# TestMule_2015.net
KiCad netlist of a schematic drawn in EAGLE
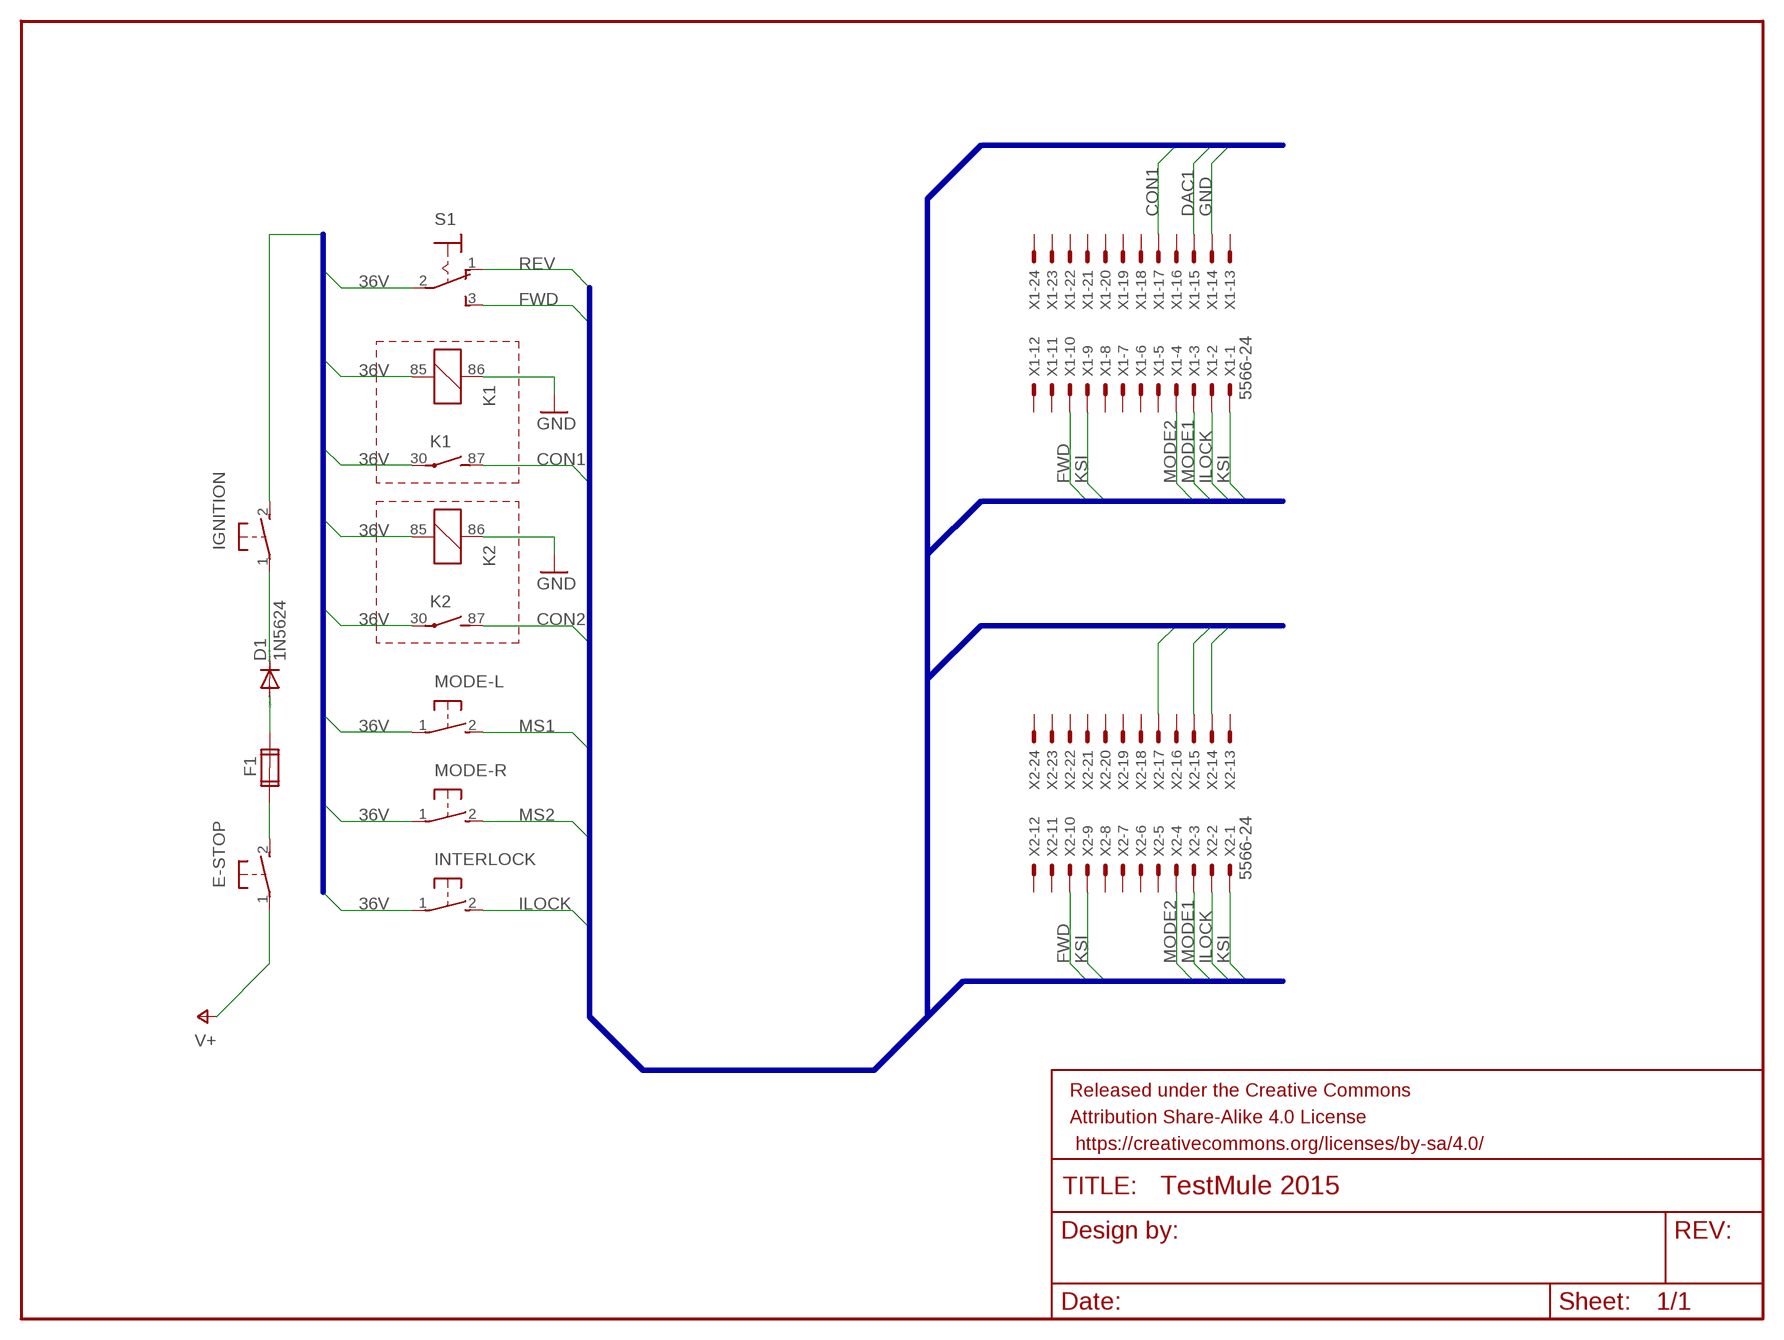
[diagram p0: schematic, sheet 1]

(export (version "E")
  (design (tool "Eeschema 10.0.6"))
  (components
    (comp (ref "D1")
      (value "1N5624")
      (footprint "eagle-import:DO201-15")
      (libsource (lib "eagle-import") (part "1N5624"))
    )
    (comp (ref "E-STOP")
      (value "31-XX")
      (footprint "eagle-import:B3F-31XX")
      (libsource (lib "eagle-import") (part "31-XX"))
    )
    (comp (ref "F1")
      (value "FUSE2P")
      (footprint "eagle-import:FUSE1")
      (libsource (lib "eagle-import") (part "FUSE2P"))
    )
    (comp (ref "FRAME1")
      (value "FRAME-LETTER")
      (footprint "eagle-import:CREATIVE_COMMONS")
      (libsource (lib "eagle-import") (part "FRAME-LETTER"))
    )
    (comp (ref "IGNITION")
      (value "31-XX")
      (footprint "eagle-import:B3F-31XX")
      (libsource (lib "eagle-import") (part "31-XX"))
    )
    (comp (ref "INTERLOCK")
      (value "31-XX")
      (footprint "eagle-import:B3F-31XX")
      (libsource (lib "eagle-import") (part "31-XX"))
    )
    (comp (ref "K1")
      (value "CB1A-P-12V")
      (footprint "eagle-import:CB1")
      (fields (field (name "MF") "AROMAT/ MATSUSHITA"))
      (libsource (lib "eagle-import") (part "CB1A-P-12V"))
    )
    (comp (ref "K2")
      (value "CB1A-P-12V")
      (footprint "eagle-import:CB1")
      (fields (field (name "MF") "AROMAT/ MATSUSHITA"))
      (libsource (lib "eagle-import") (part "CB1A-P-12V"))
    )
    (comp (ref "MODE-L")
      (value "31-XX")
      (footprint "eagle-import:B3F-31XX")
      (libsource (lib "eagle-import") (part "31-XX"))
    )
    (comp (ref "MODE-R")
      (value "31-XX")
      (footprint "eagle-import:B3F-31XX")
      (libsource (lib "eagle-import") (part "31-XX"))
    )
    (comp (ref "S1")
      (value "320-916")
      (footprint "eagle-import:320-916")
      (libsource (lib "eagle-import") (part "320-916"))
    )
    (comp (ref "X1")
      (value "5566-24")
      (footprint "eagle-import:5566-24")
      (libsource (lib "eagle-import") (part "5566-24"))
    )
    (comp (ref "X2")
      (value "5566-24")
      (footprint "eagle-import:5566-24")
      (libsource (lib "eagle-import") (part "5566-24"))
    )
  )
  (nets
    (net (code "1") (name "/36V") (class "Default")
      (node (ref "IGNITION") (pin "2") (pinfunction "S_2") (pintype "passive"))
      (node (ref "INTERLOCK") (pin "1") (pinfunction "P_1") (pintype "passive"))
      (node (ref "K1") (pin "30") (pinfunction "P_30") (pintype "passive"))
      (node (ref "K1") (pin "85") (pinfunction "2_85") (pintype "passive"))
      (node (ref "K2") (pin "30") (pinfunction "P_30") (pintype "passive"))
      (node (ref "K2") (pin "85") (pinfunction "2_85") (pintype "passive"))
      (node (ref "MODE-L") (pin "1") (pinfunction "P_1") (pintype "passive"))
      (node (ref "MODE-R") (pin "1") (pinfunction "P_1") (pintype "passive"))
      (node (ref "S1") (pin "2") (pinfunction "P_2") (pintype "passive"))
    )
    (net (code "2") (name "/CON1") (class "Default")
      (node (ref "K1") (pin "87") (pinfunction "S_87") (pintype "passive"))
      (node (ref "X1") (pin "17") (pinfunction "S_17") (pintype "passive"))
      (node (ref "X2") (pin "17") (pinfunction "S_17") (pintype "passive"))
    )
    (net (code "3") (name "/CON2") (class "Default")
      (node (ref "K2") (pin "87") (pinfunction "S_87") (pintype "passive"))
    )
    (net (code "4") (name "/DAC1") (class "Default")
      (node (ref "X1") (pin "15") (pinfunction "S_15") (pintype "passive"))
    )
    (net (code "5") (name "/FWD") (class "Default")
      (node (ref "S1") (pin "3") (pinfunction "S_3") (pintype "passive"))
      (node (ref "X1") (pin "10") (pinfunction "S_10") (pintype "passive"))
      (node (ref "X2") (pin "10") (pinfunction "S_10") (pintype "passive"))
    )
    (net (code "6") (name "/ILOCK") (class "Default")
      (node (ref "INTERLOCK") (pin "2") (pinfunction "S_2") (pintype "passive"))
      (node (ref "X1") (pin "2") (pinfunction "S_2") (pintype "passive"))
      (node (ref "X2") (pin "2") (pinfunction "S_2") (pintype "passive"))
    )
    (net (code "7") (name "/KSI") (class "Default")
      (node (ref "X1") (pin "1") (pinfunction "S_1") (pintype "passive"))
      (node (ref "X1") (pin "9") (pinfunction "S_9") (pintype "passive"))
      (node (ref "X2") (pin "1") (pinfunction "S_1") (pintype "passive"))
      (node (ref "X2") (pin "9") (pinfunction "S_9") (pintype "passive"))
    )
    (net (code "8") (name "/MODE1") (class "Default")
      (node (ref "X1") (pin "3") (pinfunction "S_3") (pintype "passive"))
      (node (ref "X2") (pin "3") (pinfunction "S_3") (pintype "passive"))
    )
    (net (code "9") (name "/MODE2") (class "Default")
      (node (ref "X1") (pin "4") (pinfunction "S_4") (pintype "passive"))
      (node (ref "X2") (pin "4") (pinfunction "S_4") (pintype "passive"))
    )
    (net (code "10") (name "/MS1") (class "Default")
      (node (ref "MODE-L") (pin "2") (pinfunction "S_2") (pintype "passive"))
    )
    (net (code "11") (name "/MS2") (class "Default")
      (node (ref "MODE-R") (pin "2") (pinfunction "S_2") (pintype "passive"))
    )
    (net (code "12") (name "/REV") (class "Default")
      (node (ref "S1") (pin "1") (pinfunction "O_1") (pintype "passive"))
    )
    (net (code "13") (name "GND") (class "Default")
      (node (ref "K1") (pin "86") (pinfunction "1_86") (pintype "passive"))
      (node (ref "K2") (pin "86") (pinfunction "1_86") (pintype "passive"))
      (node (ref "X1") (pin "14") (pinfunction "S_14") (pintype "passive"))
      (node (ref "X2") (pin "14") (pinfunction "S_14") (pintype "passive"))
    )
    (net (code "14") (name "Net-(D1-PadA)") (class "Default")
      (node (ref "D1") (pin "A") (pinfunction "A_A") (pintype "passive"))
      (node (ref "F1") (pin "2A") (pinfunction "2A_2A") (pintype "passive"))
    )
    (net (code "15") (name "Net-(E-STOP-S)") (class "Default")
      (node (ref "E-STOP") (pin "2") (pinfunction "S_2") (pintype "passive"))
      (node (ref "F1") (pin "1A") (pinfunction "1A_1A") (pintype "passive"))
    )
    (net (code "16") (name "Net-(IGNITION-P)") (class "Default")
      (node (ref "D1") (pin "C") (pinfunction "C_C") (pintype "passive"))
      (node (ref "IGNITION") (pin "1") (pinfunction "P_1") (pintype "passive"))
    )
    (net (code "17") (name "V+") (class "Default")
      (node (ref "E-STOP") (pin "1") (pinfunction "P_1") (pintype "passive"))
    )
    (net (code "18") (name "unconnected-(F1-Pad1B)") (class "Default")
      (node (ref "F1") (pin "1B") (pinfunction "1B_1B") (pintype "passive"))
    )
    (net (code "19") (name "unconnected-(F1-Pad2B)") (class "Default")
      (node (ref "F1") (pin "2B") (pinfunction "2B_2B") (pintype "passive"))
    )
    (net (code "20") (name "unconnected-(X1C-S-Pad11)") (class "Default")
      (node (ref "X1") (pin "11") (pinfunction "S_11") (pintype "passive"))
    )
    (net (code "21") (name "unconnected-(X1D-S-Pad12)") (class "Default")
      (node (ref "X1") (pin "12") (pinfunction "S_12") (pintype "passive"))
    )
    (net (code "22") (name "unconnected-(X1E-S-Pad13)") (class "Default")
      (node (ref "X1") (pin "13") (pinfunction "S_13") (pintype "passive"))
    )
    (net (code "23") (name "unconnected-(X1H-S-Pad16)") (class "Default")
      (node (ref "X1") (pin "16") (pinfunction "S_16") (pintype "passive"))
    )
    (net (code "24") (name "unconnected-(X1J-S-Pad18)") (class "Default")
      (node (ref "X1") (pin "18") (pinfunction "S_18") (pintype "passive"))
    )
    (net (code "25") (name "unconnected-(X1K-S-Pad19)") (class "Default")
      (node (ref "X1") (pin "19") (pinfunction "S_19") (pintype "passive"))
    )
    (net (code "26") (name "unconnected-(X1M-S-Pad20)") (class "Default")
      (node (ref "X1") (pin "20") (pinfunction "S_20") (pintype "passive"))
    )
    (net (code "27") (name "unconnected-(X1N-S-Pad21)") (class "Default")
      (node (ref "X1") (pin "21") (pinfunction "S_21") (pintype "passive"))
    )
    (net (code "28") (name "unconnected-(X1O-S-Pad22)") (class "Default")
      (node (ref "X1") (pin "22") (pinfunction "S_22") (pintype "passive"))
    )
    (net (code "29") (name "unconnected-(X1P-S-Pad23)") (class "Default")
      (node (ref "X1") (pin "23") (pinfunction "S_23") (pintype "passive"))
    )
    (net (code "30") (name "unconnected-(X1Q-S-Pad24)") (class "Default")
      (node (ref "X1") (pin "24") (pinfunction "S_24") (pintype "passive"))
    )
    (net (code "31") (name "unconnected-(X1T-S-Pad5)") (class "Default")
      (node (ref "X1") (pin "5") (pinfunction "S_5") (pintype "passive"))
    )
    (net (code "32") (name "unconnected-(X1U-S-Pad6)") (class "Default")
      (node (ref "X1") (pin "6") (pinfunction "S_6") (pintype "passive"))
    )
    (net (code "33") (name "unconnected-(X1V-S-Pad7)") (class "Default")
      (node (ref "X1") (pin "7") (pinfunction "S_7") (pintype "passive"))
    )
    (net (code "34") (name "unconnected-(X1W-S-Pad8)") (class "Default")
      (node (ref "X1") (pin "8") (pinfunction "S_8") (pintype "passive"))
    )
    (net (code "35") (name "unconnected-(X2C-S-Pad11)") (class "Default")
      (node (ref "X2") (pin "11") (pinfunction "S_11") (pintype "passive"))
    )
    (net (code "36") (name "unconnected-(X2D-S-Pad12)") (class "Default")
      (node (ref "X2") (pin "12") (pinfunction "S_12") (pintype "passive"))
    )
    (net (code "37") (name "unconnected-(X2E-S-Pad13)") (class "Default")
      (node (ref "X2") (pin "13") (pinfunction "S_13") (pintype "passive"))
    )
    (net (code "38") (name "unconnected-(X2G-S-Pad15)") (class "Default")
      (node (ref "X2") (pin "15") (pinfunction "S_15") (pintype "passive"))
    )
    (net (code "39") (name "unconnected-(X2H-S-Pad16)") (class "Default")
      (node (ref "X2") (pin "16") (pinfunction "S_16") (pintype "passive"))
    )
    (net (code "40") (name "unconnected-(X2J-S-Pad18)") (class "Default")
      (node (ref "X2") (pin "18") (pinfunction "S_18") (pintype "passive"))
    )
    (net (code "41") (name "unconnected-(X2K-S-Pad19)") (class "Default")
      (node (ref "X2") (pin "19") (pinfunction "S_19") (pintype "passive"))
    )
    (net (code "42") (name "unconnected-(X2M-S-Pad20)") (class "Default")
      (node (ref "X2") (pin "20") (pinfunction "S_20") (pintype "passive"))
    )
    (net (code "43") (name "unconnected-(X2N-S-Pad21)") (class "Default")
      (node (ref "X2") (pin "21") (pinfunction "S_21") (pintype "passive"))
    )
    (net (code "44") (name "unconnected-(X2O-S-Pad22)") (class "Default")
      (node (ref "X2") (pin "22") (pinfunction "S_22") (pintype "passive"))
    )
    (net (code "45") (name "unconnected-(X2P-S-Pad23)") (class "Default")
      (node (ref "X2") (pin "23") (pinfunction "S_23") (pintype "passive"))
    )
    (net (code "46") (name "unconnected-(X2Q-S-Pad24)") (class "Default")
      (node (ref "X2") (pin "24") (pinfunction "S_24") (pintype "passive"))
    )
    (net (code "47") (name "unconnected-(X2T-S-Pad5)") (class "Default")
      (node (ref "X2") (pin "5") (pinfunction "S_5") (pintype "passive"))
    )
    (net (code "48") (name "unconnected-(X2U-S-Pad6)") (class "Default")
      (node (ref "X2") (pin "6") (pinfunction "S_6") (pintype "passive"))
    )
    (net (code "49") (name "unconnected-(X2V-S-Pad7)") (class "Default")
      (node (ref "X2") (pin "7") (pinfunction "S_7") (pintype "passive"))
    )
    (net (code "50") (name "unconnected-(X2W-S-Pad8)") (class "Default")
      (node (ref "X2") (pin "8") (pinfunction "S_8") (pintype "passive"))
    )
  )
)
